# BeaglePhone_Rev2_SCH.net
KiCad netlist of a schematic drawn in Altium Designer
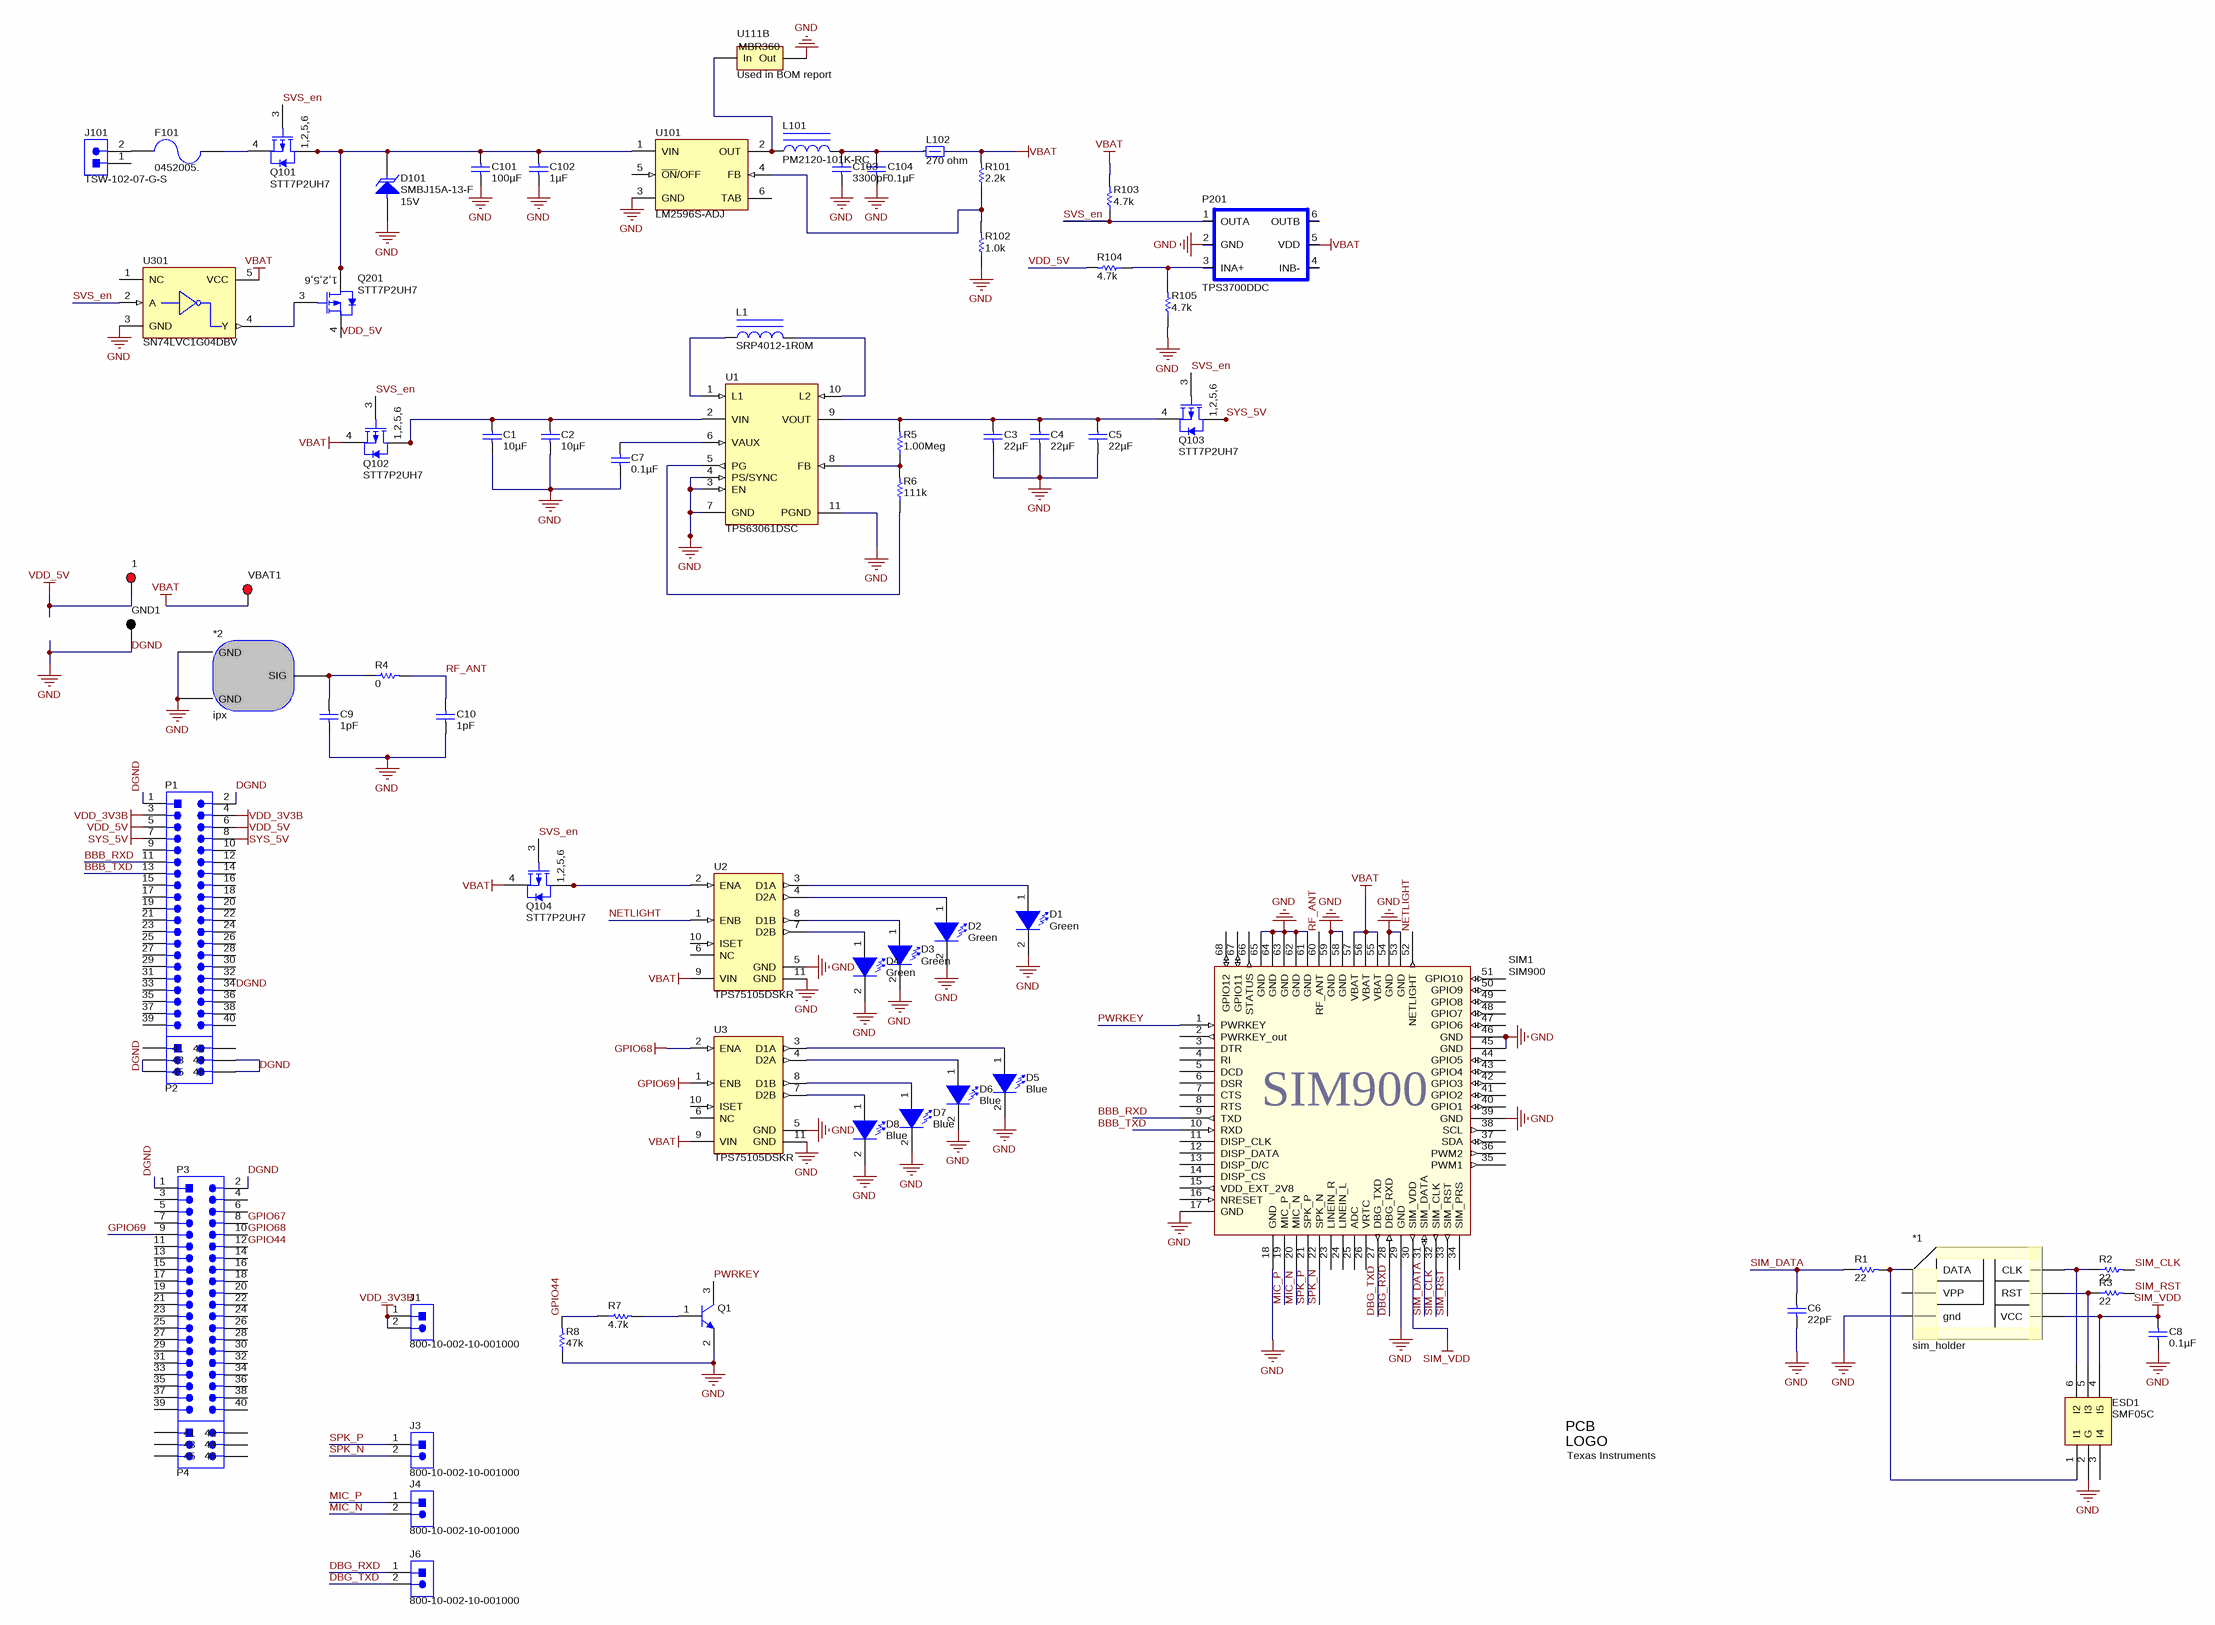
[diagram p0: BeaglePhone_Rev2_SCH.SchDoc]

(export (version "E")
  (design (tool "Eeschema 10.0.6"))
  (components
    (comp (ref "*1")
      (value "sim_holder")
      (footprint "SIM_socket")
      (libsource (lib "sim_holder") (part "sim_holder"))
    )
    (comp (ref "*2") (value "ipx") (footprint "IPX_U.FL") (libsource (lib "u.fl_IPX_connector") (part "ipx")))
    (comp (ref "1")
      (value "5005")
      (footprint "Keystone5005")
      (description "Test Point, TH, Compact, Red")
      (fields
        (field (name "MANUFACTURER") "Keystone")
        (field (name "DIGIKEYPARTNUMBER") "5005K-ND")
        (field (name "PUBLISHER") "Texas Instruments")
      )
      (libsource (lib "TemplateSCHLib") (part "5005"))
    )
    (comp (ref "C1")
      (value "C1608X5R1A106M")
      (footprint "0603")
      (description "CAP, CERM, 10uF, 10V, +/-20%, X5R, 0603")
      (fields
        (field (name "VALUEDISPLAYED") "10µF")
        (field (name "MANUFACTURER") "TDK")
        (field (name "PUBLISHER") "Texas Instruments")
      )
      (libsource (lib "Capacitor_Ceramic") (part "C1608X5R1A106M"))
    )
    (comp (ref "C2")
      (value "C1608X5R1A106M")
      (footprint "0603")
      (description "CAP, CERM, 10uF, 10V, +/-20%, X5R, 0603")
      (fields
        (field (name "VALUEDISPLAYED") "10µF")
        (field (name "MANUFACTURER") "TDK")
        (field (name "PUBLISHER") "Texas Instruments")
      )
      (libsource (lib "Capacitor_Ceramic") (part "C1608X5R1A106M"))
    )
    (comp (ref "C3")
      (value "C1608X5R0G226M080AA")
      (footprint "0603")
      (description "CAP, CERM, 22uF, 4V, +/-20%, X5R, 0603")
      (fields
        (field (name "VALUEDISPLAYED") "22µF")
        (field (name "MANUFACTURER") "TDK")
        (field (name "PUBLISHER") "Texas Instruments")
      )
      (libsource (lib "Capacitor_Ceramic") (part "C1608X5R0G226M080AA"))
    )
    (comp (ref "C4")
      (value "C1608X5R0G226M080AA")
      (footprint "0603")
      (description "CAP, CERM, 22uF, 4V, +/-20%, X5R, 0603")
      (fields
        (field (name "VALUEDISPLAYED") "22µF")
        (field (name "MANUFACTURER") "TDK")
        (field (name "PUBLISHER") "Texas Instruments")
      )
      (libsource (lib "Capacitor_Ceramic") (part "C1608X5R0G226M080AA"))
    )
    (comp (ref "C5")
      (value "C1608X5R0G226M080AA")
      (footprint "0603")
      (description "CAP, CERM, 22uF, 4V, +/-20%, X5R, 0603")
      (fields
        (field (name "VALUEDISPLAYED") "22µF")
        (field (name "MANUFACTURER") "TDK")
        (field (name "PUBLISHER") "Texas Instruments")
      )
      (libsource (lib "Capacitor_Ceramic") (part "C1608X5R0G226M080AA"))
    )
    (comp (ref "C6")
      (value "GRM1885C2A220JA01D")
      (footprint "0603")
      (description "CAP, CERM, 22pF, 100V, +/-5%, C0G/NP0, 0603")
      (fields
        (field (name "VALUEDISPLAYED") "22pF")
        (field (name "MANUFACTURER") "MuRata")
        (field (name "PUBLISHER") "Texas Instruments")
      )
      (libsource (lib "Capacitor_Ceramic") (part "GRM1885C2A220JA01D"))
    )
    (comp (ref "C7")
      (value "C0603X104K3RACTU")
      (footprint "0603")
      (description "CAP, CERM, 0.1uF, 25V, +/-10%, X7R, 0603")
      (fields
        (field (name "VALUEDISPLAYED") "0.1µF")
        (field (name "MANUFACTURER") "Kemet")
        (field (name "PUBLISHER") "Texas Instruments")
      )
      (libsource (lib "Capacitor_Ceramic") (part "C0603X104K3RACTU"))
    )
    (comp (ref "C8")
      (value "06035C104KAT2A")
      (footprint "0603")
      (description "CAP, CERM, 0.1 µF, 50 V, +/- 10%, X7R, 0603")
      (fields
        (field (name "VALUEDISPLAYED") "0.1µF")
        (field (name "MANUFACTURER") "AVX")
        (field (name "PUBLISHER") "Texas Instruments")
      )
      (libsource (lib "Capacitor_Ceramic") (part "06035C104KAT2A"))
    )
    (comp (ref "C9")
      (value "C0603C109C5GACTU")
      (footprint "0603")
      (description "CAP, CERM, 1pF, 50V, +/-25%, C0G/NP0, 0603")
      (fields
        (field (name "VALUEDISPLAYED") "1pF")
        (field (name "MANUFACTURER") "Kemet")
        (field (name "PUBLISHER") "Texas Instruments")
      )
      (libsource (lib "Capacitor_Ceramic") (part "C0603C109C5GACTU"))
    )
    (comp (ref "C10")
      (value "C0603C109C5GACTU")
      (footprint "0603")
      (description "CAP, CERM, 1pF, 50V, +/-25%, C0G/NP0, 0603")
      (fields
        (field (name "VALUEDISPLAYED") "1pF")
        (field (name "MANUFACTURER") "Kemet")
        (field (name "PUBLISHER") "Texas Instruments")
      )
      (libsource (lib "Capacitor_Ceramic") (part "C0603C109C5GACTU"))
    )
    (comp (ref "C101")
      (value "GRM31CR60J107ME39L")
      (footprint "1206")
      (description "CAP, CERM, 100uF, 6.3V, +/-20%, X5R, 1206")
      (fields
        (field (name "VALUEDISPLAYED") "100µF")
        (field (name "MANUFACTURER") "MuRata")
        (field (name "PUBLISHER") "Texas Instruments")
      )
      (libsource (lib "Capacitor_Ceramic") (part "GRM31CR60J107ME39L"))
    )
    (comp (ref "C102")
      (value "GRM188R61A105KA61D")
      (footprint "0603")
      (description "CAP, CERM, 1uF, 10V, +/-10%, X5R, 0603")
      (fields
        (field (name "VALUEDISPLAYED") "1µF")
        (field (name "MANUFACTURER") "MuRata")
        (field (name "PUBLISHER") "Texas Instruments")
      )
      (libsource (lib "Capacitor_Ceramic") (part "GRM188R61A105KA61D"))
    )
    (comp (ref "C103")
      (value "GRM188R71H332KA01D")
      (footprint "0603")
      (description "CAP, CERM, 3300pF, 50V, +/-10%, X7R, 0603")
      (fields
        (field (name "VALUEDISPLAYED") "3300pF")
        (field (name "MANUFACTURER") "MuRata")
        (field (name "PUBLISHER") "Texas Instruments")
      )
      (libsource (lib "Capacitor_Ceramic") (part "GRM188R71H332KA01D"))
    )
    (comp (ref "C104")
      (value "C0603X104K4RACTU")
      (footprint "0603")
      (description "CAP, CERM, 0.1uF, 16V, +/-10%, X7R, 0603")
      (fields
        (field (name "VALUEDISPLAYED") "0.1µF")
        (field (name "MANUFACTURER") "Kemet")
        (field (name "PUBLISHER") "Texas Instruments")
      )
      (libsource (lib "Capacitor_Ceramic") (part "C0603X104K4RACTU"))
    )
    (comp (ref "D1")
      (value "Green")
      (footprint "LG L29K_GREEN")
      (description "LED, Green, SMD")
      (fields
        (field (name "MANUFACTURER") "OSRAM")
        (field (name "PARTNUMBER") "LG L29K-G2J1-24-Z")
        (field (name "PUBLISHER") "Texas Instruments")
      )
      (libsource (lib "LED") (part "LG L29K-G2J1-24-Z"))
    )
    (comp (ref "D2")
      (value "Green")
      (footprint "LG L29K_GREEN")
      (description "LED, Green, SMD")
      (fields
        (field (name "MANUFACTURER") "OSRAM")
        (field (name "PARTNUMBER") "LG L29K-G2J1-24-Z")
        (field (name "PUBLISHER") "Texas Instruments")
      )
      (libsource (lib "LED") (part "LG L29K-G2J1-24-Z"))
    )
    (comp (ref "D3")
      (value "Green")
      (footprint "LG L29K_GREEN")
      (description "LED, Green, SMD")
      (fields
        (field (name "MANUFACTURER") "OSRAM")
        (field (name "PARTNUMBER") "LG L29K-G2J1-24-Z")
        (field (name "PUBLISHER") "Texas Instruments")
      )
      (libsource (lib "LED") (part "LG L29K-G2J1-24-Z"))
    )
    (comp (ref "D4")
      (value "Green")
      (footprint "LG L29K_GREEN")
      (description "LED, Green, SMD")
      (fields
        (field (name "MANUFACTURER") "OSRAM")
        (field (name "PARTNUMBER") "LG L29K-G2J1-24-Z")
        (field (name "PUBLISHER") "Texas Instruments")
      )
      (libsource (lib "LED") (part "LG L29K-G2J1-24-Z"))
    )
    (comp (ref "D5")
      (value "Blue")
      (footprint "LB Q39G_BLUE")
      (description "LED, Blue, SMD")
      (fields
        (field (name "MANUFACTURER") "OSRAM")
        (field (name "PARTNUMBER") "LB Q39G-L2N2-35-1")
        (field (name "PUBLISHER") "Texas Instruments")
      )
      (libsource (lib "LED") (part "LB Q39G-L2N2-35-1"))
    )
    (comp (ref "D6")
      (value "Blue")
      (footprint "LB Q39G_BLUE")
      (description "LED, Blue, SMD")
      (fields
        (field (name "MANUFACTURER") "OSRAM")
        (field (name "PARTNUMBER") "LB Q39G-L2N2-35-1")
        (field (name "PUBLISHER") "Texas Instruments")
      )
      (libsource (lib "LED") (part "LB Q39G-L2N2-35-1"))
    )
    (comp (ref "D7")
      (value "Blue")
      (footprint "LB Q39G_BLUE")
      (description "LED, Blue, SMD")
      (fields
        (field (name "MANUFACTURER") "OSRAM")
        (field (name "PARTNUMBER") "LB Q39G-L2N2-35-1")
        (field (name "PUBLISHER") "Texas Instruments")
      )
      (libsource (lib "LED") (part "LB Q39G-L2N2-35-1"))
    )
    (comp (ref "D8")
      (value "Blue")
      (footprint "LB Q39G_BLUE")
      (description "LED, Blue, SMD")
      (fields
        (field (name "MANUFACTURER") "OSRAM")
        (field (name "PARTNUMBER") "LB Q39G-L2N2-35-1")
        (field (name "PUBLISHER") "Texas Instruments")
      )
      (libsource (lib "LED") (part "LB Q39G-L2N2-35-1"))
    )
    (comp (ref "D101")
      (value "SMBJ15A-13-F")
      (footprint "SMB")
      (description "Diode, TVS, Uni, 15V, 600W, SMB")
      (fields
        (field (name "ALTIUM_VALUE") "15V")
        (field (name "MANUFACTURER") "Diodes Inc.")
        (field (name "PUBLISHER") "Texas Instruments")
      )
      (libsource (lib "ZenerDiodes") (part "SMBJ15A-13-F"))
    )
    (comp (ref "ESD1") (value "SMF05C") (footprint "6pin") (libsource (lib "SMF05C") (part "SMF05C")))
    (comp (ref "F101")
      (value "0452005.")
      (footprint "SloBlo452")
      (description "Fuse, 5A, 125V, SMD")
      (fields (field (name "MANUFACTURER") "Littelfuse") (field (name "PUBLISHER") "Texas Instruments"))
      (libsource (lib "Fuse") (part "0452005."))
    )
    (comp (ref "GND1")
      (value "5006")
      (footprint "Keystone5006")
      (description "Test Point, TH, Compact, Black")
      (fields
        (field (name "MANUFACTURER") "Keystone")
        (field (name "DIGIKEYPARTNUMBER") "5006K-ND")
        (field (name "PUBLISHER") "Texas Instruments")
      )
      (libsource (lib "TemplateSCHLib") (part "5006"))
    )
    (comp (ref "J1")
      (value "800-10-002-10-001000")
      (footprint "Mill-Max_800-10-002-10-001000")
      (description "Header, 2x1, 100mil, SMT")
      (fields
        (field (name "MANUFACTURER") "Mill-Max")
        (field (name "SYMBOLCREATOR") "a0412235")
        (field (name "PUBLISHER") "Texas Instruments")
      )
      (libsource (lib "Connectors") (part "800-10-002-10-001000"))
    )
    (comp (ref "J3")
      (value "800-10-002-10-001000")
      (footprint "Mill-Max_800-10-002-10-001000")
      (description "Header, 2x1, 100mil, SMT")
      (fields
        (field (name "MANUFACTURER") "Mill-Max")
        (field (name "SYMBOLCREATOR") "a0412235")
        (field (name "PUBLISHER") "Texas Instruments")
      )
      (libsource (lib "Connectors") (part "800-10-002-10-001000"))
    )
    (comp (ref "J4")
      (value "800-10-002-10-001000")
      (footprint "Mill-Max_800-10-002-10-001000")
      (description "Header, 2x1, 100mil, SMT")
      (fields
        (field (name "MANUFACTURER") "Mill-Max")
        (field (name "SYMBOLCREATOR") "a0412235")
        (field (name "PUBLISHER") "Texas Instruments")
      )
      (libsource (lib "Connectors") (part "800-10-002-10-001000"))
    )
    (comp (ref "J6")
      (value "800-10-002-10-001000")
      (footprint "Mill-Max_800-10-002-10-001000")
      (description "Header, 2x1, 100mil, SMT")
      (fields
        (field (name "MANUFACTURER") "Mill-Max")
        (field (name "SYMBOLCREATOR") "a0412235")
        (field (name "PUBLISHER") "Texas Instruments")
      )
      (libsource (lib "Connectors") (part "800-10-002-10-001000"))
    )
    (comp (ref "J101")
      (value "TSW-102-07-G-S")
      (footprint "TSW-102-07-G-S")
      (description "Header, 100mil, 2x1, Gold, TH")
      (fields
        (field (name "MANUFACTURER") "Samtec")
        (field (name "SYMBOLCREATOR") "a0412235")
        (field (name "PUBLISHER") "Texas Instruments")
      )
      (libsource (lib "Connectors") (part "TSW-102-07-G-S"))
    )
    (comp (ref "L1")
      (value "SRP4012-1R0M")
      (footprint "SRP4012")
      (description "Inductor, Flat Wire, Powdered Iron, 1uH, 4.8A, 0.0336 ohm, SMD")
      (fields (field (name "MANUFACTURER") "Bourns") (field (name "PUBLISHER") "Texas Instruments"))
      (libsource (lib "Inductor_Bourns") (part "SRP4012-1R0M"))
    )
    (comp (ref "L101")
      (value "PM2120-101K-RC")
      (footprint "PM2120")
      (description "Inductor, Toroid, 100uH, 6.1A, 0.035 ohm, SMD")
      (fields (field (name "MANUFACTURER") "Bourns") (field (name "PUBLISHER") "Texas Instruments"))
      (libsource (lib "Inductor_Bourns") (part "PM2120-101K-RC"))
    )
    (comp (ref "L102")
      (value "270 ohm")
      (footprint "2220")
      (description "Ferrite Bead, 270 ohm @ 100MHz, 4A, 2220")
      (fields
        (field (name "PARTNUMBER") "HI2220P271R-10")
        (field (name "MANUFACTURER") "Laird-Signal Integrity Products")
        (field (name "PUBLISHER") "Texas Instruments")
      )
      (libsource (lib "FerriteBead") (part "HI2220P271R-10"))
    )
    (comp (ref "Logo1")
      (value "Texas Instruments")
      (footprint "TI_Symbol_Overlay_Small")
      (description "Texas Instrument Corporate Signature")
      (fields (field (name "SYMBOLCREATOR") "codlsc") (field (name "PUBLISHER") "Texas Instruments"))
      (libsource (lib "Logos") (part "TI_Logo"))
    )
    (comp (ref "P1")
      (value "Comment")
      (footprint "TSW-120-07-G-D")
      (description "Header, 100mil, 20x2, Gold, TH")
      (fields
        (field (name "PARTNUMBER") "TSW-120-07-G-D")
        (field (name "MANUFACTURER") "Samtec")
        (field (name "SYMBOLCREATOR") "a0412235")
        (field (name "PUBLISHER") "Texas Instruments")
      )
      (libsource (lib "Connectors") (part "TSW-120-07-G-D"))
    )
    (comp (ref "P2")
      (value "Comment")
      (footprint "SULLINS_PEC03DAAN")
      (description "Header, 100mil, 3x2, Tin, TH")
      (fields
        (field (name "PARTNUMBER") "PEC03DAAN")
        (field (name "MANUFACTURER") "Sullins Connector Solutions")
        (field (name "SYMBOLCREATOR") "a0412235")
        (field (name "PUBLISHER") "Texas Instruments")
      )
      (libsource (lib "Connectors") (part "PEC03DAAN"))
    )
    (comp (ref "P3")
      (value "Comment")
      (footprint "TSW-120-07-G-D")
      (description "Header, 100mil, 20x2, Gold, TH")
      (fields
        (field (name "PARTNUMBER") "TSW-120-07-G-D")
        (field (name "MANUFACTURER") "Samtec")
        (field (name "SYMBOLCREATOR") "a0412235")
        (field (name "PUBLISHER") "Texas Instruments")
      )
      (libsource (lib "Connectors") (part "TSW-120-07-G-D"))
    )
    (comp (ref "P4")
      (value "Comment")
      (footprint "SULLINS_PEC03DAAN")
      (description "Header, 100mil, 3x2, Tin, TH")
      (fields
        (field (name "PARTNUMBER") "PEC03DAAN")
        (field (name "MANUFACTURER") "Sullins Connector Solutions")
        (field (name "SYMBOLCREATOR") "a0412235")
        (field (name "PUBLISHER") "Texas Instruments")
      )
      (libsource (lib "Connectors") (part "PEC03DAAN"))
    )
    (comp (ref "P201")
      (value "TPS3700DDC")
      (footprint "SOT23-6")
      (description "IC,  High Voltage, Over-Under Voltage Supervisory")
      (fields (field (name "MANUFACTURER") "TI"))
      (libsource (lib "PADSlegacy_PMP") (part "TPS3700DDC"))
    )
    (comp (ref "Q1")
      (value "MMBT2222LT1G")
      (footprint "SOT-23")
      (description "Transistor, NPN, 30V, 0.6A, SOT-23")
      (fields (field (name "MANUFACTURER") "ON Semiconductor") (field (name "PUBLISHER") "Texas Instruments"))
      (libsource (lib "Bipolar_Transistor") (part "MMBT2222LT1G, ON Semiconductor"))
    )
    (comp (ref "Q101")
      (value "STT7P2UH7")
      (footprint "SOT-23-6")
      (description "MOSFET, P-CH, 60V, -3A, SOT-23-6")
      (fields
        (field (name "MANUFACTURER") "Fairchild Semiconductor")
        (field (name "PUBLISHER") "Texas Instruments")
      )
      (libsource (lib "FETs") (part "FDC5614P"))
    )
    (comp (ref "Q102")
      (value "STT7P2UH7")
      (footprint "SOT-23-6")
      (description "MOSFET, P-CH, 60V, -3A, SOT-23-6")
      (fields
        (field (name "MANUFACTURER") "Fairchild Semiconductor")
        (field (name "PUBLISHER") "Texas Instruments")
      )
      (libsource (lib "FETs") (part "FDC5614P"))
    )
    (comp (ref "Q103")
      (value "STT7P2UH7")
      (footprint "SOT-23-6")
      (description "MOSFET, P-CH, 60V, -3A, SOT-23-6")
      (fields
        (field (name "MANUFACTURER") "Fairchild Semiconductor")
        (field (name "PUBLISHER") "Texas Instruments")
      )
      (libsource (lib "FETs") (part "FDC5614P"))
    )
    (comp (ref "Q104")
      (value "STT7P2UH7")
      (footprint "SOT-23-6")
      (description "MOSFET, P-CH, 60V, -3A, SOT-23-6")
      (fields
        (field (name "MANUFACTURER") "Fairchild Semiconductor")
        (field (name "PUBLISHER") "Texas Instruments")
      )
      (libsource (lib "FETs") (part "FDC5614P"))
    )
    (comp (ref "Q201")
      (value "STT7P2UH7")
      (footprint "SOT-23-6")
      (description "MOSFET, P-CH, 60V, -3A, SOT-23-6")
      (fields
        (field (name "MANUFACTURER") "Fairchild Semiconductor")
        (field (name "PUBLISHER") "Texas Instruments")
      )
      (libsource (lib "FETs") (part "FDC5614P"))
    )
    (comp (ref "R1")
      (value "22")
      (footprint "0603")
      (description "RES, 22 ohm, 5%, 0.1W, 0603")
      (fields
        (field (name "PARTNUMBER") "CRCW060322R0JNEA")
        (field (name "MANUFACTURER") "Vishay-Dale")
        (field (name "PUBLISHER") "Texas Instruments")
      )
      (libsource (lib "Resistor_0603") (part "CRCW060322R0JNEA"))
    )
    (comp (ref "R2")
      (value "22")
      (footprint "0603")
      (description "RES, 22 ohm, 5%, 0.1W, 0603")
      (fields
        (field (name "PARTNUMBER") "CRCW060322R0JNEA")
        (field (name "MANUFACTURER") "Vishay-Dale")
        (field (name "PUBLISHER") "Texas Instruments")
      )
      (libsource (lib "Resistor_0603") (part "CRCW060322R0JNEA"))
    )
    (comp (ref "R3")
      (value "22")
      (footprint "0603")
      (description "RES, 22 ohm, 5%, 0.1W, 0603")
      (fields
        (field (name "PARTNUMBER") "CRCW060322R0JNEA")
        (field (name "MANUFACTURER") "Vishay-Dale")
        (field (name "PUBLISHER") "Texas Instruments")
      )
      (libsource (lib "Resistor_0603") (part "CRCW060322R0JNEA"))
    )
    (comp (ref "R4")
      (value "0")
      (footprint "0805_HV")
      (description "RES, 0 ohm, 5%, 0.333W, 0805")
      (fields
        (field (name "PARTNUMBER") "CRCW08050000Z0EAHP")
        (field (name "MANUFACTURER") "Vishay-Dale")
        (field (name "PUBLISHER") "Texas Instruments")
      )
      (libsource (lib "Resistor_0805") (part "CRCW08050000Z0EAHP"))
    )
    (comp (ref "R5")
      (value "1.00Meg")
      (footprint "0603")
      (description "RES, 1.00Meg ohm, 1%, 0.1W, 0603")
      (fields
        (field (name "PARTNUMBER") "CRCW06031M00FKEA")
        (field (name "MANUFACTURER") "Vishay-Dale")
        (field (name "PUBLISHER") "Texas Instruments")
      )
      (libsource (lib "Resistor_0603") (part "CRCW06031M00FKEA"))
    )
    (comp (ref "R6")
      (value "111k")
      (footprint "0603")
      (description "RES, 111k ohm, 0.1%, 0.1W, 0603")
      (fields
        (field (name "PARTNUMBER") "RT0603BRD07111KL")
        (field (name "MANUFACTURER") "Yageo America")
        (field (name "PUBLISHER") "Texas Instruments")
      )
      (libsource (lib "Resistor_0603") (part "RT0603BRD07111KL"))
    )
    (comp (ref "R7")
      (value "CRCW04024K70JNED")
      (footprint "0402")
      (description "RES, 4.7 k, 5%, 0.063 W, 0402")
      (fields
        (field (name "VALUEDISPLAYED") "4.7k")
        (field (name "MANUFACTURER") "Vishay-Dale")
        (field (name "PUBLISHER") "Texas Instruments")
      )
      (libsource (lib "Resistor_0402") (part "CRCW04024K70JNED"))
    )
    (comp (ref "R8")
      (value "CRCW04024K70JNED")
      (footprint "0402")
      (description "RES, 4.7 k, 5%, 0.063 W, 0402")
      (fields
        (field (name "VALUEDISPLAYED") "47k")
        (field (name "MANUFACTURER") "Vishay-Dale")
        (field (name "PUBLISHER") "Texas Instruments")
      )
      (libsource (lib "Resistor_0402") (part "CRCW04024K70JNED"))
    )
    (comp (ref "R101")
      (value "2.2k")
      (footprint "0603")
      (description "RES, 2.2k ohm, 5%, 0.1W, 0603")
      (fields
        (field (name "PARTNUMBER") "CRCW06032K20JNEA")
        (field (name "MANUFACTURER") "Vishay-Dale")
        (field (name "PUBLISHER") "Texas Instruments")
      )
      (libsource (lib "Resistor_0603") (part "CRCW06032K20JNEA"))
    )
    (comp (ref "R102")
      (value "1.0k")
      (footprint "0603")
      (description "RES, 1.0k ohm, 5%, 0.1W, 0603")
      (fields
        (field (name "PARTNUMBER") "CRCW06031K00JNEA")
        (field (name "MANUFACTURER") "Vishay-Dale")
        (field (name "PUBLISHER") "Texas Instruments")
      )
      (libsource (lib "Resistor_0603") (part "CRCW06031K00JNEA"))
    )
    (comp (ref "R103")
      (value "4.7k")
      (footprint "0603")
      (description "RES, 4.7k ohm, 5%, 0.1W, 0603")
      (fields
        (field (name "PARTNUMBER") "CRCW06034K70JNEA")
        (field (name "MANUFACTURER") "Vishay-Dale")
        (field (name "PUBLISHER") "Texas Instruments")
      )
      (libsource (lib "Resistor_0603") (part "CRCW06034K70JNEA"))
    )
    (comp (ref "R104")
      (value "4.7k")
      (footprint "0603")
      (description "RES, 4.7k ohm, 5%, 0.1W, 0603")
      (fields
        (field (name "PARTNUMBER") "CRCW06034K70JNEA")
        (field (name "MANUFACTURER") "Vishay-Dale")
        (field (name "PUBLISHER") "Texas Instruments")
      )
      (libsource (lib "Resistor_0603") (part "CRCW06034K70JNEA"))
    )
    (comp (ref "R105")
      (value "4.7k")
      (footprint "0603")
      (description "RES, 4.7k ohm, 5%, 0.1W, 0603")
      (fields
        (field (name "PARTNUMBER") "CRCW06034K70JNEA")
        (field (name "MANUFACTURER") "Vishay-Dale")
        (field (name "PUBLISHER") "Texas Instruments")
      )
      (libsource (lib "Resistor_0603") (part "CRCW06034K70JNEA"))
    )
    (comp (ref "SIM1")
      (value "SIM900")
      (footprint "PCBComponent_1 - duplicate1")
      (libsource (lib "Schematic Components") (part "SIM900"))
    )
    (comp (ref "U1")
      (value "TPS63061DSC")
      (footprint "DSC0010E")
      (description "HIGH INPUT VOLTAGE BUCK-BOOST CONVERTER WITH 2A SWITCH CURRENT, DSC0010E")
      (fields
        (field (name "MANUFACTURER") "Texas Instruments")
        (field (name "SYMBOLCREATOR") "a0411947")
        (field (name "PUBLISHER") "Texas Instruments")
      )
      (libsource (lib "TI_Pre_Release") (part "TPS63061DSC"))
    )
    (comp (ref "U2")
      (value "TPS75105DSKR")
      (footprint "DSK0010A")
      (fields
        (field (name "MANUFACTURER") "Texas Instruments")
        (field (name "ALTERNATE PARTNUMBER") "Equivalent")
      )
      (libsource (lib "TI Power Management Lighting and Display") (part "TPS75105DSKR"))
    )
    (comp (ref "U3")
      (value "TPS75105DSKR")
      (footprint "DSK0010A")
      (fields
        (field (name "MANUFACTURER") "Texas Instruments")
        (field (name "ALTERNATE PARTNUMBER") "Equivalent")
      )
      (libsource (lib "TI Power Management Lighting and Display") (part "TPS75105DSKR"))
    )
    (comp (ref "U101")
      (value "LM2596S-ADJ")
      (footprint "TS5B_N")
      (description "SIMPLE SWITCHER® Power Converter 150 KHz 3A Step-Down Voltage Regulator, 5-pin TO-263")
      (fields
        (field (name "MANUFACTURER") "National Semiconductor")
        (field (name "PUBLISHER") "Altium Limited")
      )
      (libsource (lib "NSC Switcher") (part "LM2596S-ADJ"))
    )
    (comp (ref "U111")
      (value "Used in BOM report")
      (footprint "PCBComponent_1 - duplicate2")
      (fields (field (name "SYMBOLCREATOR") "Use a-id"))
      (libsource (lib "josh") (part "MBR360"))
    )
    (comp (ref "U301")
      (value "SN74LVC1G04DBV")
      (footprint "DBV0005A_N")
      (description "Single Inverter Gate, DBV0005A")
      (fields
        (field (name "MANUFACTURER") "Texas Instruments")
        (field (name "SYMBOLCREATOR") "a0411947")
        (field (name "PUBLISHER") "Texas Instruments")
      )
      (libsource (lib "TI_Pre_Release") (part "SN74LVC1G04DBV"))
    )
    (comp (ref "VBAT1")
      (value "5005")
      (footprint "Keystone5005")
      (description "Test Point, TH, Compact, Red")
      (fields
        (field (name "MANUFACTURER") "Keystone")
        (field (name "DIGIKEYPARTNUMBER") "5005K-ND")
        (field (name "PUBLISHER") "Texas Instruments")
      )
      (libsource (lib "TemplateSCHLib") (part "5005"))
    )
  )
  (nets
    (net (code "2") (name "/BBB_RXD") (class "Default")
      (node (ref "P1") (pin "11") (pinfunction "11_11") (pintype "passive"))
    )
    (net (code "3") (name "/BBB_TXD") (class "Default")
      (node (ref "P1") (pin "13") (pinfunction "13_13") (pintype "passive"))
    )
    (net (code "4") (name "/DBG_RXD") (class "Default")
      (node (ref "J6") (pin "1") (pinfunction "1_1") (pintype "passive"))
      (node (ref "SIM1") (pin "28") (pinfunction "DBG_RXD_28") (pintype "input"))
    )
    (net (code "5") (name "/DBG_TXD") (class "Default")
      (node (ref "J6") (pin "2") (pinfunction "2_2") (pintype "passive"))
      (node (ref "SIM1") (pin "27") (pinfunction "DBG_TXD_27") (pintype "output"))
    )
    (net (code "6") (name "/GPIO44") (class "Default")
      (node (ref "P3") (pin "12") (pinfunction "12_12") (pintype "passive"))
      (node (ref "R7") (pin "1") (pinfunction "1_1") (pintype "passive"))
      (node (ref "R8") (pin "2") (pinfunction "2_2") (pintype "passive"))
    )
    (net (code "7") (name "/GPIO67") (class "Default")
      (node (ref "P3") (pin "8") (pinfunction "8_8") (pintype "passive"))
    )
    (net (code "8") (name "/MIC_N") (class "Default")
      (node (ref "J4") (pin "2") (pinfunction "2_2") (pintype "passive"))
      (node (ref "SIM1") (pin "20") (pinfunction "MIC_N_20") (pintype "passive"))
    )
    (net (code "9") (name "/MIC_P") (class "Default")
      (node (ref "J4") (pin "1") (pinfunction "1_1") (pintype "passive"))
      (node (ref "SIM1") (pin "19") (pinfunction "MIC_P_19") (pintype "passive"))
    )
    (net (code "10") (name "/NETLIGHT") (class "Default")
      (node (ref "SIM1") (pin "52") (pinfunction "NETLIGHT_52") (pintype "output"))
      (node (ref "U2") (pin "1") (pinfunction "ENB_1") (pintype "input"))
    )
    (net (code "11") (name "/PWRKEY") (class "Default")
      (node (ref "Q1") (pin "3") (pinfunction "C_3") (pintype "passive"))
      (node (ref "SIM1") (pin "1") (pinfunction "PWRKEY_1") (pintype "input"))
    )
    (net (code "12") (name "/RF_ANT") (class "Default")
      (node (ref "C10") (pin "1") (pinfunction "1_1") (pintype "passive"))
      (node (ref "R4") (pin "2") (pinfunction "2_2") (pintype "passive"))
      (node (ref "SIM1") (pin "60") (pinfunction "RF_ANT_60") (pintype "passive"))
    )
    (net (code "13") (name "/SIM_CLK") (class "Default")
      (node (ref "R2") (pin "2") (pinfunction "2_2") (pintype "passive"))
      (node (ref "SIM1") (pin "32") (pinfunction "SIM_CLK_32") (pintype "output"))
    )
    (net (code "14") (name "/SIM_DATA") (class "Default")
      (node (ref "C6") (pin "1") (pinfunction "1_1") (pintype "passive"))
      (node (ref "R1") (pin "1") (pinfunction "1_1") (pintype "passive"))
      (node (ref "SIM1") (pin "31") (pinfunction "SIM_DATA_31") (pintype "bidirectional"))
    )
    (net (code "15") (name "/SIM_RST") (class "Default")
      (node (ref "R3") (pin "2") (pinfunction "2_2") (pintype "passive"))
      (node (ref "SIM1") (pin "33") (pinfunction "SIM_RST_33") (pintype "output"))
    )
    (net (code "16") (name "/SPK_N") (class "Default")
      (node (ref "J3") (pin "2") (pinfunction "2_2") (pintype "passive"))
      (node (ref "SIM1") (pin "22") (pinfunction "SPK_N_22") (pintype "passive"))
    )
    (net (code "17") (name "/SPK_P") (class "Default")
      (node (ref "J3") (pin "1") (pinfunction "1_1") (pintype "passive"))
      (node (ref "SIM1") (pin "21") (pinfunction "SPK_P_21") (pintype "passive"))
    )
    (net (code "18") (name "/SVS_en") (class "Default")
      (node (ref "P201") (pin "1") (pinfunction "OUTA_1") (pintype "passive"))
      (node (ref "Q101") (pin "3") (pinfunction "G_3") (pintype "passive"))
      (node (ref "Q102") (pin "3") (pinfunction "G_3") (pintype "passive"))
      (node (ref "Q103") (pin "3") (pinfunction "G_3") (pintype "passive"))
      (node (ref "Q104") (pin "3") (pinfunction "G_3") (pintype "passive"))
      (node (ref "R103") (pin "1") (pinfunction "1_1") (pintype "passive"))
      (node (ref "U301") (pin "2") (pinfunction "A_2") (pintype "input"))
    )
    (net (code "19") (name "GND") (class "Default")
      (node (ref "*1") (pin "1") (pinfunction "gnd_1") (pintype "passive"))
      (node (ref "*2") (pin "1") (pinfunction "GND_1") (pintype "passive"))
      (node (ref "*2") (pin "2") (pinfunction "GND_2") (pintype "passive"))
      (node (ref "C1") (pin "1") (pinfunction "1_1") (pintype "passive"))
      (node (ref "C10") (pin "2") (pinfunction "2_2") (pintype "passive"))
      (node (ref "C101") (pin "2") (pinfunction "2_2") (pintype "passive"))
      (node (ref "C102") (pin "2") (pinfunction "2_2") (pintype "passive"))
      (node (ref "C103") (pin "2") (pinfunction "2_2") (pintype "passive"))
      (node (ref "C104") (pin "2") (pinfunction "2_2") (pintype "passive"))
      (node (ref "C2") (pin "1") (pinfunction "1_1") (pintype "passive"))
      (node (ref "C3") (pin "1") (pinfunction "1_1") (pintype "passive"))
      (node (ref "C4") (pin "1") (pinfunction "1_1") (pintype "passive"))
      (node (ref "C5") (pin "1") (pinfunction "1_1") (pintype "passive"))
      (node (ref "C6") (pin "2") (pinfunction "2_2") (pintype "passive"))
      (node (ref "C7") (pin "2") (pinfunction "2_2") (pintype "passive"))
      (node (ref "C8") (pin "2") (pinfunction "2_2") (pintype "passive"))
      (node (ref "C9") (pin "2") (pinfunction "2_2") (pintype "passive"))
      (node (ref "D1") (pin "2") (pinfunction "K_2") (pintype "passive"))
      (node (ref "D101") (pin "2") (pinfunction "A_2") (pintype "passive"))
      (node (ref "D2") (pin "2") (pinfunction "K_2") (pintype "passive"))
      (node (ref "D3") (pin "2") (pinfunction "K_2") (pintype "passive"))
      (node (ref "D4") (pin "2") (pinfunction "K_2") (pintype "passive"))
      (node (ref "D5") (pin "2") (pinfunction "K_2") (pintype "passive"))
      (node (ref "D6") (pin "2") (pinfunction "K_2") (pintype "passive"))
      (node (ref "D7") (pin "2") (pinfunction "K_2") (pintype "passive"))
      (node (ref "D8") (pin "2") (pinfunction "K_2") (pintype "passive"))
      (node (ref "ESD1") (pin "2") (pinfunction "G_2") (pintype "passive"))
      (node (ref "GND1") (pin "1") (pintype "passive"))
      (node (ref "P1") (pin "1") (pinfunction "1_1") (pintype "passive"))
      (node (ref "P1") (pin "2") (pinfunction "2_2") (pintype "passive"))
      (node (ref "P1") (pin "34") (pinfunction "34_34") (pintype "passive"))
      (node (ref "P2") (pin "3") (pinfunction "43_3") (pintype "passive"))
      (node (ref "P2") (pin "4") (pinfunction "44_4") (pintype "passive"))
      (node (ref "P2") (pin "5") (pinfunction "45_5") (pintype "passive"))
      (node (ref "P2") (pin "6") (pinfunction "46_6") (pintype "passive"))
      (node (ref "P201") (pin "2") (pinfunction "GND_2") (pintype "passive"))
      (node (ref "P3") (pin "1") (pinfunction "1_1") (pintype "passive"))
      (node (ref "P3") (pin "2") (pinfunction "2_2") (pintype "passive"))
      (node (ref "Q1") (pin "2") (pinfunction "E_2") (pintype "passive"))
      (node (ref "R102") (pin "1") (pinfunction "1_1") (pintype "passive"))
      (node (ref "R105") (pin "1") (pinfunction "1_1") (pintype "passive"))
      (node (ref "R8") (pin "1") (pinfunction "1_1") (pintype "passive"))
      (node (ref "SIM1") (pin "17") (pinfunction "GND_17") (pintype "passive"))
      (node (ref "SIM1") (pin "18") (pinfunction "GND_18") (pintype "passive"))
      (node (ref "SIM1") (pin "29") (pinfunction "GND_29") (pintype "passive"))
      (node (ref "SIM1") (pin "39") (pinfunction "GND_39") (pintype "passive"))
      (node (ref "SIM1") (pin "45") (pinfunction "GND_45") (pintype "passive"))
      (node (ref "SIM1") (pin "46") (pinfunction "GND_46") (pintype "passive"))
      (node (ref "SIM1") (pin "53") (pinfunction "GND_53") (pintype "passive"))
      (node (ref "SIM1") (pin "54") (pinfunction "GND_54") (pintype "passive"))
      (node (ref "SIM1") (pin "58") (pinfunction "GND_58") (pintype "passive"))
      (node (ref "SIM1") (pin "59") (pinfunction "GND_59") (pintype "passive"))
      (node (ref "SIM1") (pin "61") (pinfunction "GND_61") (pintype "passive"))
      (node (ref "SIM1") (pin "62") (pinfunction "GND_62") (pintype "passive"))
      (node (ref "SIM1") (pin "63") (pinfunction "GND_63") (pintype "passive"))
      (node (ref "SIM1") (pin "64") (pinfunction "GND_64") (pintype "passive"))
      (node (ref "SIM1") (pin "65") (pinfunction "GND_65") (pintype "passive"))
      (node (ref "U1") (pin "11") (pinfunction "PGND_11") (pintype "power_in"))
      (node (ref "U1") (pin "3") (pinfunction "EN_3") (pintype "input"))
      (node (ref "U1") (pin "4") (pinfunction "PS/SYNC_4") (pintype "input"))
      (node (ref "U1") (pin "7") (pinfunction "GND_7") (pintype "power_in"))
      (node (ref "U101") (pin "3") (pinfunction "GND_3") (pintype "power_in"))
      (node (ref "U111") (pin "2") (pinfunction "Out_2") (pintype "passive"))
      (node (ref "U2") (pin "11") (pinfunction "GND_11") (pintype "power_in"))
      (node (ref "U2") (pin "5") (pinfunction "GND_5") (pintype "power_in"))
      (node (ref "U3") (pin "11") (pinfunction "GND_11") (pintype "power_in"))
      (node (ref "U3") (pin "5") (pinfunction "GND_5") (pintype "power_in"))
      (node (ref "U301") (pin "3") (pinfunction "GND_3") (pintype "power_in"))
    )
    (net (code "20") (name "GPIO68") (class "Default")
      (node (ref "P3") (pin "10") (pinfunction "10_10") (pintype "passive"))
      (node (ref "U3") (pin "2") (pinfunction "ENA_2") (pintype "input"))
    )
    (net (code "21") (name "GPIO69") (class "Default")
      (node (ref "P3") (pin "9") (pinfunction "9_9") (pintype "passive"))
      (node (ref "U3") (pin "1") (pinfunction "ENB_1") (pintype "input"))
    )
    (net (code "22") (name "Net-(*1-CLK)") (class "Default")
      (node (ref "*1") (pin "4") (pinfunction "CLK_4") (pintype "passive"))
      (node (ref "ESD1") (pin "6") (pinfunction "I2_6") (pintype "passive"))
      (node (ref "R2") (pin "1") (pinfunction "1_1") (pintype "passive"))
    )
    (net (code "23") (name "Net-(*1-DATA)") (class "Default")
      (node (ref "*1") (pin "3") (pinfunction "DATA_3") (pintype "passive"))
      (node (ref "ESD1") (pin "1") (pinfunction "I1_1") (pintype "passive"))
      (node (ref "R1") (pin "2") (pinfunction "2_2") (pintype "passive"))
    )
    (net (code "24") (name "Net-(*1-RST)") (class "Default")
      (node (ref "*1") (pin "5") (pinfunction "RST_5") (pintype "passive"))
      (node (ref "ESD1") (pin "5") (pinfunction "I3_5") (pintype "passive"))
      (node (ref "R3") (pin "1") (pinfunction "1_1") (pintype "passive"))
    )
    (net (code "25") (name "Net-(*2-SIG)") (class "Default")
      (node (ref "*2") (pin "3") (pinfunction "SIG_3") (pintype "passive"))
      (node (ref "C9") (pin "1") (pinfunction "1_1") (pintype "passive"))
      (node (ref "R4") (pin "1") (pinfunction "1_1") (pintype "passive"))
    )
    (net (code "26") (name "Net-(C103-Pad1)") (class "Default")
      (node (ref "C103") (pin "1") (pinfunction "1_1") (pintype "passive"))
      (node (ref "C104") (pin "1") (pinfunction "1_1") (pintype "passive"))
      (node (ref "L101") (pin "2") (pinfunction "2_2") (pintype "passive"))
      (node (ref "L102") (pin "1") (pinfunction "1_1") (pintype "passive"))
    )
    (net (code "27") (name "Net-(D1-A)") (class "Default")
      (node (ref "D1") (pin "1") (pinfunction "A_1") (pintype "passive"))
      (node (ref "U2") (pin "3") (pinfunction "D1A_3") (pintype "output"))
    )
    (net (code "28") (name "Net-(D2-A)") (class "Default")
      (node (ref "D2") (pin "1") (pinfunction "A_1") (pintype "passive"))
      (node (ref "U2") (pin "4") (pinfunction "D2A_4") (pintype "output"))
    )
    (net (code "29") (name "Net-(D3-A)") (class "Default")
      (node (ref "D3") (pin "1") (pinfunction "A_1") (pintype "passive"))
      (node (ref "U2") (pin "8") (pinfunction "D1B_8") (pintype "output"))
    )
    (net (code "30") (name "Net-(D4-A)") (class "Default")
      (node (ref "D4") (pin "1") (pinfunction "A_1") (pintype "passive"))
      (node (ref "U2") (pin "7") (pinfunction "D2B_7") (pintype "output"))
    )
    (net (code "31") (name "Net-(D5-A)") (class "Default")
      (node (ref "D5") (pin "1") (pinfunction "A_1") (pintype "passive"))
      (node (ref "U3") (pin "3") (pinfunction "D1A_3") (pintype "output"))
    )
    (net (code "32") (name "Net-(D6-A)") (class "Default")
      (node (ref "D6") (pin "1") (pinfunction "A_1") (pintype "passive"))
      (node (ref "U3") (pin "4") (pinfunction "D2A_4") (pintype "output"))
    )
    (net (code "33") (name "Net-(D7-A)") (class "Default")
      (node (ref "D7") (pin "1") (pinfunction "A_1") (pintype "passive"))
      (node (ref "U3") (pin "8") (pinfunction "D1B_8") (pintype "output"))
    )
    (net (code "34") (name "Net-(D8-A)") (class "Default")
      (node (ref "D8") (pin "1") (pinfunction "A_1") (pintype "passive"))
      (node (ref "U3") (pin "7") (pinfunction "D2B_7") (pintype "output"))
    )
    (net (code "35") (name "Net-(D101-K)") (class "Default")
      (node (ref "C101") (pin "1") (pinfunction "1_1") (pintype "passive"))
      (node (ref "C102") (pin "1") (pinfunction "1_1") (pintype "passive"))
      (node (ref "D101") (pin "1") (pinfunction "K_1") (pintype "passive"))
      (node (ref "Q101") (pin "1") (pinfunction "D_1") (pintype "passive"))
      (node (ref "Q101") (pin "2") (pinfunction "D_2") (pintype "passive"))
      (node (ref "Q101") (pin "5") (pinfunction "D_5") (pintype "passive"))
      (node (ref "Q101") (pin "6") (pinfunction "D_6") (pintype "passive"))
      (node (ref "Q201") (pin "1") (pinfunction "D_1") (pintype "passive"))
      (node (ref "Q201") (pin "2") (pinfunction "D_2") (pintype "passive"))
      (node (ref "Q201") (pin "5") (pinfunction "D_5") (pintype "passive"))
      (node (ref "Q201") (pin "6") (pinfunction "D_6") (pintype "passive"))
      (node (ref "U101") (pin "1") (pinfunction "VIN_1") (pintype "power_in"))
    )
    (net (code "36") (name "Net-(F101-Pad2)") (class "Default")
      (node (ref "F101") (pin "2") (pinfunction "2_2") (pintype "passive"))
      (node (ref "J101") (pin "2") (pinfunction "2_2") (pintype "passive"))
    )
    (net (code "37") (name "Net-(P201-INA+)") (class "Default")
      (node (ref "P201") (pin "3") (pinfunction "INA+_3") (pintype "passive"))
      (node (ref "R104") (pin "1") (pinfunction "1_1") (pintype "passive"))
      (node (ref "R105") (pin "2") (pinfunction "2_2") (pintype "passive"))
    )
    (net (code "38") (name "Net-(Q1-B)") (class "Default")
      (node (ref "Q1") (pin "1") (pinfunction "B_1") (pintype "passive"))
      (node (ref "R7") (pin "2") (pinfunction "2_2") (pintype "passive"))
    )
    (net (code "39") (name "Net-(Q101-S)") (class "Default")
      (node (ref "F101") (pin "1") (pinfunction "1_1") (pintype "passive"))
      (node (ref "Q101") (pin "4") (pinfunction "S_4") (pintype "passive"))
    )
    (net (code "40") (name "Net-(Q103-S)") (class "Default")
      (node (ref "C3") (pin "2") (pinfunction "2_2") (pintype "passive"))
      (node (ref "C4") (pin "2") (pinfunction "2_2") (pintype "passive"))
      (node (ref "C5") (pin "2") (pinfunction "2_2") (pintype "passive"))
      (node (ref "Q103") (pin "4") (pinfunction "S_4") (pintype "passive"))
      (node (ref "R5") (pin "2") (pinfunction "2_2") (pintype "passive"))
      (node (ref "U1") (pin "9") (pinfunction "VOUT_9") (pintype "power_in"))
    )
    (net (code "41") (name "Net-(Q201-G)") (class "Default")
      (node (ref "Q201") (pin "3") (pinfunction "G_3") (pintype "passive"))
      (node (ref "U301") (pin "4") (pinfunction "Y_4") (pintype "output"))
    )
    (net (code "42") (name "Net-(U1-FB)") (class "Default")
      (node (ref "R5") (pin "1") (pinfunction "1_1") (pintype "passive"))
      (node (ref "R6") (pin "2") (pinfunction "2_2") (pintype "passive"))
      (node (ref "U1") (pin "8") (pinfunction "FB_8") (pintype "input"))
    )
    (net (code "43") (name "Net-(U1-L1)") (class "Default")
      (node (ref "L1") (pin "1") (pinfunction "1_1") (pintype "passive"))
      (node (ref "U1") (pin "1") (pinfunction "L1_1") (pintype "input"))
    )
    (net (code "44") (name "Net-(U1-L2)") (class "Default")
      (node (ref "L1") (pin "2") (pinfunction "2_2") (pintype "passive"))
      (node (ref "U1") (pin "10") (pinfunction "L2_10") (pintype "input"))
    )
    (net (code "45") (name "Net-(U1-PG)") (class "Default")
      (node (ref "R6") (pin "1") (pinfunction "1_1") (pintype "passive"))
      (node (ref "U1") (pin "5") (pinfunction "PG_5") (pintype "output"))
    )
    (net (code "46") (name "Net-(U1-VAUX)") (class "Default")
      (node (ref "C7") (pin "1") (pinfunction "1_1") (pintype "passive"))
      (node (ref "U1") (pin "6") (pinfunction "VAUX_6") (pintype "input"))
    )
    (net (code "47") (name "Net-(U1-VIN)") (class "Default")
      (node (ref "C1") (pin "2") (pinfunction "2_2") (pintype "passive"))
      (node (ref "C2") (pin "2") (pinfunction "2_2") (pintype "passive"))
      (node (ref "Q102") (pin "1") (pinfunction "D_1") (pintype "passive"))
      (node (ref "Q102") (pin "2") (pinfunction "D_2") (pintype "passive"))
      (node (ref "Q102") (pin "5") (pinfunction "D_5") (pintype "passive"))
      (node (ref "Q102") (pin "6") (pinfunction "D_6") (pintype "passive"))
      (node (ref "U1") (pin "2") (pinfunction "VIN_2") (pintype "power_in"))
    )
    (net (code "48") (name "Net-(U2-ENA)") (class "Default")
      (node (ref "Q104") (pin "1") (pinfunction "D_1") (pintype "passive"))
      (node (ref "Q104") (pin "2") (pinfunction "D_2") (pintype "passive"))
      (node (ref "Q104") (pin "5") (pinfunction "D_5") (pintype "passive"))
      (node (ref "Q104") (pin "6") (pinfunction "D_6") (pintype "passive"))
      (node (ref "U2") (pin "2") (pinfunction "ENA_2") (pintype "input"))
    )
    (net (code "49") (name "Net-(U101-FB)") (class "Default")
      (node (ref "R101") (pin "1") (pinfunction "1_1") (pintype "passive"))
      (node (ref "R102") (pin "2") (pinfunction "2_2") (pintype "passive"))
      (node (ref "U101") (pin "4") (pinfunction "FB_4") (pintype "input"))
    )
    (net (code "50") (name "Net-(U101-OUT)") (class "Default")
      (node (ref "L101") (pin "1") (pinfunction "1_1") (pintype "passive"))
      (node (ref "U101") (pin "2") (pinfunction "OUT_2") (pintype "power_in"))
      (node (ref "U111") (pin "1") (pinfunction "In_1") (pintype "passive"))
    )
    (net (code "51") (name "SIM_VDD") (class "Default")
      (node (ref "*1") (pin "6") (pinfunction "VCC_6") (pintype "passive"))
      (node (ref "C8") (pin "1") (pinfunction "1_1") (pintype "passive"))
      (node (ref "ESD1") (pin "4") (pinfunction "I5_4") (pintype "passive"))
      (node (ref "SIM1") (pin "30") (pinfunction "SIM_VDD_30") (pintype "output"))
    )
    (net (code "52") (name "SYS_5V") (class "Default")
      (node (ref "P1") (pin "7") (pinfunction "7_7") (pintype "passive"))
      (node (ref "P1") (pin "8") (pinfunction "8_8") (pintype "passive"))
      (node (ref "Q103") (pin "1") (pinfunction "D_1") (pintype "passive"))
      (node (ref "Q103") (pin "2") (pinfunction "D_2") (pintype "passive"))
      (node (ref "Q103") (pin "5") (pinfunction "D_5") (pintype "passive"))
      (node (ref "Q103") (pin "6") (pinfunction "D_6") (pintype "passive"))
    )
    (net (code "53") (name "VBAT") (class "Default")
      (node (ref "L102") (pin "2") (pinfunction "2_2") (pintype "passive"))
      (node (ref "P201") (pin "5") (pinfunction "VDD_5") (pintype "passive"))
      (node (ref "Q102") (pin "4") (pinfunction "S_4") (pintype "passive"))
      (node (ref "Q104") (pin "4") (pinfunction "S_4") (pintype "passive"))
      (node (ref "R101") (pin "2") (pinfunction "2_2") (pintype "passive"))
      (node (ref "R103") (pin "2") (pinfunction "2_2") (pintype "passive"))
      (node (ref "SIM1") (pin "55") (pinfunction "VBAT_55") (pintype "power_in"))
      (node (ref "SIM1") (pin "56") (pinfunction "VBAT_56") (pintype "power_in"))
      (node (ref "SIM1") (pin "57") (pinfunction "VBAT_57") (pintype "power_in"))
      (node (ref "U2") (pin "9") (pinfunction "VIN_9") (pintype "power_in"))
      (node (ref "U3") (pin "9") (pinfunction "VIN_9") (pintype "power_in"))
      (node (ref "U301") (pin "5") (pinfunction "VCC_5") (pintype "power_in"))
      (node (ref "VBAT1") (pin "1") (pintype "passive"))
    )
    (net (code "54") (name "VDD_3V3B") (class "Default")
      (node (ref "J1") (pin "1") (pinfunction "1_1") (pintype "passive"))
      (node (ref "J1") (pin "2") (pinfunction "2_2") (pintype "passive"))
      (node (ref "P1") (pin "3") (pinfunction "3_3") (pintype "passive"))
      (node (ref "P1") (pin "4") (pinfunction "4_4") (pintype "passive"))
    )
    (net (code "55") (name "VDD_5V") (class "Default")
      (node (ref "1") (pin "1") (pintype "passive"))
      (node (ref "P1") (pin "5") (pinfunction "5_5") (pintype "passive"))
      (node (ref "P1") (pin "6") (pinfunction "6_6") (pintype "passive"))
      (node (ref "Q201") (pin "4") (pinfunction "S_4") (pintype "passive"))
      (node (ref "R104") (pin "2") (pinfunction "2_2") (pintype "passive"))
    )
    (net (code "56") (name "unconnected-(*1-VPP-Pad2)") (class "Default")
      (node (ref "*1") (pin "2") (pinfunction "VPP_2") (pintype "passive"))
    )
    (net (code "57") (name "unconnected-(ESD1-I4-Pad3)") (class "Default")
      (node (ref "ESD1") (pin "3") (pinfunction "I4_3") (pintype "passive"))
    )
    (net (code "58") (name "unconnected-(J101-Pad1)") (class "Default")
      (node (ref "J101") (pin "1") (pinfunction "1_1") (pintype "passive"))
    )
    (net (code "59") (name "unconnected-(P1-Pad9)") (class "Default")
      (node (ref "P1") (pin "9") (pinfunction "9_9") (pintype "passive"))
    )
    (net (code "60") (name "unconnected-(P1-Pad10)") (class "Default")
      (node (ref "P1") (pin "10") (pinfunction "10_10") (pintype "passive"))
    )
    (net (code "61") (name "unconnected-(P1-Pad12)") (class "Default")
      (node (ref "P1") (pin "12") (pinfunction "12_12") (pintype "passive"))
    )
    (net (code "62") (name "unconnected-(P1-Pad14)") (class "Default")
      (node (ref "P1") (pin "14") (pinfunction "14_14") (pintype "passive"))
    )
    (net (code "63") (name "unconnected-(P1-Pad15)") (class "Default")
      (node (ref "P1") (pin "15") (pinfunction "15_15") (pintype "passive"))
    )
    (net (code "64") (name "unconnected-(P1-Pad16)") (class "Default")
      (node (ref "P1") (pin "16") (pinfunction "16_16") (pintype "passive"))
    )
    (net (code "65") (name "unconnected-(P1-Pad17)") (class "Default")
      (node (ref "P1") (pin "17") (pinfunction "17_17") (pintype "passive"))
    )
    (net (code "66") (name "unconnected-(P1-Pad18)") (class "Default")
      (node (ref "P1") (pin "18") (pinfunction "18_18") (pintype "passive"))
    )
    (net (code "67") (name "unconnected-(P1-Pad19)") (class "Default")
      (node (ref "P1") (pin "19") (pinfunction "19_19") (pintype "passive"))
    )
    (net (code "68") (name "unconnected-(P1-Pad20)") (class "Default")
      (node (ref "P1") (pin "20") (pinfunction "20_20") (pintype "passive"))
    )
    (net (code "69") (name "unconnected-(P1-Pad21)") (class "Default")
      (node (ref "P1") (pin "21") (pinfunction "21_21") (pintype "passive"))
    )
    (net (code "70") (name "unconnected-(P1-Pad22)") (class "Default")
      (node (ref "P1") (pin "22") (pinfunction "22_22") (pintype "passive"))
    )
    (net (code "71") (name "unconnected-(P1-Pad23)") (class "Default")
      (node (ref "P1") (pin "23") (pinfunction "23_23") (pintype "passive"))
    )
    (net (code "72") (name "unconnected-(P1-Pad24)") (class "Default")
      (node (ref "P1") (pin "24") (pinfunction "24_24") (pintype "passive"))
    )
    (net (code "73") (name "unconnected-(P1-Pad25)") (class "Default")
      (node (ref "P1") (pin "25") (pinfunction "25_25") (pintype "passive"))
    )
    (net (code "74") (name "unconnected-(P1-Pad26)") (class "Default")
      (node (ref "P1") (pin "26") (pinfunction "26_26") (pintype "passive"))
    )
    (net (code "75") (name "unconnected-(P1-Pad27)") (class "Default")
      (node (ref "P1") (pin "27") (pinfunction "27_27") (pintype "passive"))
    )
    (net (code "76") (name "unconnected-(P1-Pad28)") (class "Default")
      (node (ref "P1") (pin "28") (pinfunction "28_28") (pintype "passive"))
    )
    (net (code "77") (name "unconnected-(P1-Pad29)") (class "Default")
      (node (ref "P1") (pin "29") (pinfunction "29_29") (pintype "passive"))
    )
    (net (code "78") (name "unconnected-(P1-Pad30)") (class "Default")
      (node (ref "P1") (pin "30") (pinfunction "30_30") (pintype "passive"))
    )
    (net (code "79") (name "unconnected-(P1-Pad31)") (class "Default")
      (node (ref "P1") (pin "31") (pinfunction "31_31") (pintype "passive"))
    )
    (net (code "80") (name "unconnected-(P1-Pad32)") (class "Default")
      (node (ref "P1") (pin "32") (pinfunction "32_32") (pintype "passive"))
    )
    (net (code "81") (name "unconnected-(P1-Pad33)") (class "Default")
      (node (ref "P1") (pin "33") (pinfunction "33_33") (pintype "passive"))
    )
    (net (code "82") (name "unconnected-(P1-Pad35)") (class "Default")
      (node (ref "P1") (pin "35") (pinfunction "35_35") (pintype "passive"))
    )
    (net (code "83") (name "unconnected-(P1-Pad36)") (class "Default")
      (node (ref "P1") (pin "36") (pinfunction "36_36") (pintype "passive"))
    )
    (net (code "84") (name "unconnected-(P1-Pad37)") (class "Default")
      (node (ref "P1") (pin "37") (pinfunction "37_37") (pintype "passive"))
    )
    (net (code "85") (name "unconnected-(P1-Pad38)") (class "Default")
      (node (ref "P1") (pin "38") (pinfunction "38_38") (pintype "passive"))
    )
    (net (code "86") (name "unconnected-(P1-Pad39)") (class "Default")
      (node (ref "P1") (pin "39") (pinfunction "39_39") (pintype "passive"))
    )
    (net (code "87") (name "unconnected-(P1-Pad40)") (class "Default")
      (node (ref "P1") (pin "40") (pinfunction "40_40") (pintype "passive"))
    )
    (net (code "88") (name "unconnected-(P2-41-Pad1)") (class "Default")
      (node (ref "P2") (pin "1") (pinfunction "41_1") (pintype "passive"))
    )
    (net (code "89") (name "unconnected-(P2-42-Pad2)") (class "Default")
      (node (ref "P2") (pin "2") (pinfunction "42_2") (pintype "passive"))
    )
    (net (code "90") (name "unconnected-(P3-Pad3)") (class "Default")
      (node (ref "P3") (pin "3") (pinfunction "3_3") (pintype "passive"))
    )
    (net (code "91") (name "unconnected-(P3-Pad4)") (class "Default")
      (node (ref "P3") (pin "4") (pinfunction "4_4") (pintype "passive"))
    )
    (net (code "92") (name "unconnected-(P3-Pad5)") (class "Default")
      (node (ref "P3") (pin "5") (pinfunction "5_5") (pintype "passive"))
    )
    (net (code "93") (name "unconnected-(P3-Pad6)") (class "Default")
      (node (ref "P3") (pin "6") (pinfunction "6_6") (pintype "passive"))
    )
    (net (code "94") (name "unconnected-(P3-Pad7)") (class "Default")
      (node (ref "P3") (pin "7") (pinfunction "7_7") (pintype "passive"))
    )
    (net (code "95") (name "unconnected-(P3-Pad11)") (class "Default")
      (node (ref "P3") (pin "11") (pinfunction "11_11") (pintype "passive"))
    )
    (net (code "96") (name "unconnected-(P3-Pad13)") (class "Default")
      (node (ref "P3") (pin "13") (pinfunction "13_13") (pintype "passive"))
    )
    (net (code "97") (name "unconnected-(P3-Pad14)") (class "Default")
      (node (ref "P3") (pin "14") (pinfunction "14_14") (pintype "passive"))
    )
    (net (code "98") (name "unconnected-(P3-Pad15)") (class "Default")
      (node (ref "P3") (pin "15") (pinfunction "15_15") (pintype "passive"))
    )
    (net (code "99") (name "unconnected-(P3-Pad16)") (class "Default")
      (node (ref "P3") (pin "16") (pinfunction "16_16") (pintype "passive"))
    )
    (net (code "100") (name "unconnected-(P3-Pad17)") (class "Default")
      (node (ref "P3") (pin "17") (pinfunction "17_17") (pintype "passive"))
    )
    (net (code "101") (name "unconnected-(P3-Pad18)") (class "Default")
      (node (ref "P3") (pin "18") (pinfunction "18_18") (pintype "passive"))
    )
    (net (code "102") (name "unconnected-(P3-Pad19)") (class "Default")
      (node (ref "P3") (pin "19") (pinfunction "19_19") (pintype "passive"))
    )
    (net (code "103") (name "unconnected-(P3-Pad20)") (class "Default")
      (node (ref "P3") (pin "20") (pinfunction "20_20") (pintype "passive"))
    )
    (net (code "104") (name "unconnected-(P3-Pad21)") (class "Default")
      (node (ref "P3") (pin "21") (pinfunction "21_21") (pintype "passive"))
    )
    (net (code "105") (name "unconnected-(P3-Pad22)") (class "Default")
      (node (ref "P3") (pin "22") (pinfunction "22_22") (pintype "passive"))
    )
    (net (code "106") (name "unconnected-(P3-Pad23)") (class "Default")
      (node (ref "P3") (pin "23") (pinfunction "23_23") (pintype "passive"))
    )
    (net (code "107") (name "unconnected-(P3-Pad24)") (class "Default")
      (node (ref "P3") (pin "24") (pinfunction "24_24") (pintype "passive"))
    )
    (net (code "108") (name "unconnected-(P3-Pad25)") (class "Default")
      (node (ref "P3") (pin "25") (pinfunction "25_25") (pintype "passive"))
    )
    (net (code "109") (name "unconnected-(P3-Pad26)") (class "Default")
      (node (ref "P3") (pin "26") (pinfunction "26_26") (pintype "passive"))
    )
    (net (code "110") (name "unconnected-(P3-Pad27)") (class "Default")
      (node (ref "P3") (pin "27") (pinfunction "27_27") (pintype "passive"))
    )
    (net (code "111") (name "unconnected-(P3-Pad28)") (class "Default")
      (node (ref "P3") (pin "28") (pinfunction "28_28") (pintype "passive"))
    )
    (net (code "112") (name "unconnected-(P3-Pad29)") (class "Default")
      (node (ref "P3") (pin "29") (pinfunction "29_29") (pintype "passive"))
    )
    (net (code "113") (name "unconnected-(P3-Pad30)") (class "Default")
      (node (ref "P3") (pin "30") (pinfunction "30_30") (pintype "passive"))
    )
    (net (code "114") (name "unconnected-(P3-Pad31)") (class "Default")
      (node (ref "P3") (pin "31") (pinfunction "31_31") (pintype "passive"))
    )
    (net (code "115") (name "unconnected-(P3-Pad32)") (class "Default")
      (node (ref "P3") (pin "32") (pinfunction "32_32") (pintype "passive"))
    )
    (net (code "116") (name "unconnected-(P3-Pad33)") (class "Default")
      (node (ref "P3") (pin "33") (pinfunction "33_33") (pintype "passive"))
    )
    (net (code "117") (name "unconnected-(P3-Pad34)") (class "Default")
      (node (ref "P3") (pin "34") (pinfunction "34_34") (pintype "passive"))
    )
    (net (code "118") (name "unconnected-(P3-Pad35)") (class "Default")
      (node (ref "P3") (pin "35") (pinfunction "35_35") (pintype "passive"))
    )
    (net (code "119") (name "unconnected-(P3-Pad36)") (class "Default")
      (node (ref "P3") (pin "36") (pinfunction "36_36") (pintype "passive"))
    )
    (net (code "120") (name "unconnected-(P3-Pad37)") (class "Default")
      (node (ref "P3") (pin "37") (pinfunction "37_37") (pintype "passive"))
    )
    (net (code "121") (name "unconnected-(P3-Pad38)") (class "Default")
      (node (ref "P3") (pin "38") (pinfunction "38_38") (pintype "passive"))
    )
    (net (code "122") (name "unconnected-(P3-Pad39)") (class "Default")
      (node (ref "P3") (pin "39") (pinfunction "39_39") (pintype "passive"))
    )
    (net (code "123") (name "unconnected-(P3-Pad40)") (class "Default")
      (node (ref "P3") (pin "40") (pinfunction "40_40") (pintype "passive"))
    )
    (net (code "124") (name "unconnected-(P4-41-Pad1)") (class "Default")
      (node (ref "P4") (pin "1") (pinfunction "41_1") (pintype "passive"))
    )
    (net (code "125") (name "unconnected-(P4-42-Pad2)") (class "Default")
      (node (ref "P4") (pin "2") (pinfunction "42_2") (pintype "passive"))
    )
    (net (code "126") (name "unconnected-(P4-43-Pad3)") (class "Default")
      (node (ref "P4") (pin "3") (pinfunction "43_3") (pintype "passive"))
    )
    (net (code "127") (name "unconnected-(P4-44-Pad4)") (class "Default")
      (node (ref "P4") (pin "4") (pinfunction "44_4") (pintype "passive"))
    )
    (net (code "128") (name "unconnected-(P4-45-Pad5)") (class "Default")
      (node (ref "P4") (pin "5") (pinfunction "45_5") (pintype "passive"))
    )
    (net (code "129") (name "unconnected-(P4-46-Pad6)") (class "Default")
      (node (ref "P4") (pin "6") (pinfunction "46_6") (pintype "passive"))
    )
    (net (code "130") (name "unconnected-(P201-INB--Pad4)") (class "Default")
      (node (ref "P201") (pin "4") (pinfunction "INB-_4") (pintype "passive"))
    )
    (net (code "131") (name "unconnected-(P201-OUTB-Pad6)") (class "Default")
      (node (ref "P201") (pin "6") (pinfunction "OUTB_6") (pintype "passive"))
    )
    (net (code "132") (name "unconnected-(SIM1-ADC-Pad25)") (class "Default")
      (node (ref "SIM1") (pin "25") (pinfunction "ADC_25") (pintype "passive"))
    )
    (net (code "133") (name "unconnected-(SIM1-CTS-Pad7)") (class "Default")
      (node (ref "SIM1") (pin "7") (pinfunction "CTS_7") (pintype "passive"))
    )
    (net (code "134") (name "unconnected-(SIM1-DCD-Pad5)") (class "Default")
      (node (ref "SIM1") (pin "5") (pinfunction "DCD_5") (pintype "passive"))
    )
    (net (code "135") (name "unconnected-(SIM1-DISP_CLK-Pad11)") (class "Default")
      (node (ref "SIM1") (pin "11") (pinfunction "DISP_CLK_11") (pintype "passive"))
    )
    (net (code "136") (name "unconnected-(SIM1-DISP_CS-Pad14)") (class "Default")
      (node (ref "SIM1") (pin "14") (pinfunction "DISP_CS_14") (pintype "passive"))
    )
    (net (code "137") (name "unconnected-(SIM1-DISP_DATA-Pad12)") (class "Default")
      (node (ref "SIM1") (pin "12") (pinfunction "DISP_DATA_12") (pintype "passive"))
    )
    (net (code "138") (name "unconnected-(SIM1-DISP_D{slash}C-Pad13)") (class "Default")
      (node (ref "SIM1") (pin "13") (pinfunction "DISP_D/C_13") (pintype "passive"))
    )
    (net (code "139") (name "unconnected-(SIM1-DSR-Pad6)") (class "Default")
      (node (ref "SIM1") (pin "6") (pinfunction "DSR_6") (pintype "passive"))
    )
    (net (code "140") (name "unconnected-(SIM1-DTR-Pad3)") (class "Default")
      (node (ref "SIM1") (pin "3") (pinfunction "DTR_3") (pintype "passive"))
    )
    (net (code "141") (name "unconnected-(SIM1-GPIO1-Pad40)") (class "Default")
      (node (ref "SIM1") (pin "40") (pinfunction "GPIO1_40") (pintype "bidirectional"))
    )
    (net (code "142") (name "unconnected-(SIM1-GPIO2-Pad41)") (class "Default")
      (node (ref "SIM1") (pin "41") (pinfunction "GPIO2_41") (pintype "bidirectional"))
    )
    (net (code "143") (name "unconnected-(SIM1-GPIO3-Pad42)") (class "Default")
      (node (ref "SIM1") (pin "42") (pinfunction "GPIO3_42") (pintype "bidirectional"))
    )
    (net (code "144") (name "unconnected-(SIM1-GPIO4-Pad43)") (class "Default")
      (node (ref "SIM1") (pin "43") (pinfunction "GPIO4_43") (pintype "bidirectional"))
    )
    (net (code "145") (name "unconnected-(SIM1-GPIO5-Pad44)") (class "Default")
      (node (ref "SIM1") (pin "44") (pinfunction "GPIO5_44") (pintype "bidirectional"))
    )
    (net (code "146") (name "unconnected-(SIM1-GPIO6-Pad47)") (class "Default")
      (node (ref "SIM1") (pin "47") (pinfunction "GPIO6_47") (pintype "bidirectional"))
    )
    (net (code "147") (name "unconnected-(SIM1-GPIO7-Pad48)") (class "Default")
      (node (ref "SIM1") (pin "48") (pinfunction "GPIO7_48") (pintype "bidirectional"))
    )
    (net (code "148") (name "unconnected-(SIM1-GPIO8-Pad49)") (class "Default")
      (node (ref "SIM1") (pin "49") (pinfunction "GPIO8_49") (pintype "bidirectional"))
    )
    (net (code "149") (name "unconnected-(SIM1-GPIO9-Pad50)") (class "Default")
      (node (ref "SIM1") (pin "50") (pinfunction "GPIO9_50") (pintype "bidirectional"))
    )
    (net (code "150") (name "unconnected-(SIM1-GPIO10-Pad51)") (class "Default")
      (node (ref "SIM1") (pin "51") (pinfunction "GPIO10_51") (pintype "bidirectional"))
    )
    (net (code "151") (name "unconnected-(SIM1-GPIO11-Pad67)") (class "Default")
      (node (ref "SIM1") (pin "67") (pinfunction "GPIO11_67") (pintype "bidirectional"))
    )
    (net (code "152") (name "unconnected-(SIM1-GPIO12-Pad68)") (class "Default")
      (node (ref "SIM1") (pin "68") (pinfunction "GPIO12_68") (pintype "bidirectional"))
    )
    (net (code "153") (name "unconnected-(SIM1-LINEIN_L-Pad24)") (class "Default")
      (node (ref "SIM1") (pin "24") (pinfunction "LINEIN_L_24") (pintype "passive"))
    )
    (net (code "154") (name "unconnected-(SIM1-LINEIN_R-Pad23)") (class "Default")
      (node (ref "SIM1") (pin "23") (pinfunction "LINEIN_R_23") (pintype "passive"))
    )
    (net (code "155") (name "unconnected-(SIM1-NRESET-Pad16)") (class "Default")
      (node (ref "SIM1") (pin "16") (pinfunction "NRESET_16") (pintype "input"))
    )
    (net (code "156") (name "unconnected-(SIM1-PWM1-Pad35)") (class "Default")
      (node (ref "SIM1") (pin "35") (pinfunction "PWM1_35") (pintype "output"))
    )
    (net (code "157") (name "unconnected-(SIM1-PWM2-Pad36)") (class "Default")
      (node (ref "SIM1") (pin "36") (pinfunction "PWM2_36") (pintype "output"))
    )
    (net (code "158") (name "unconnected-(SIM1-PWRKEY_out-Pad2)") (class "Default")
      (node (ref "SIM1") (pin "2") (pinfunction "PWRKEY_out_2") (pintype "output"))
    )
    (net (code "159") (name "unconnected-(SIM1-RI-Pad4)") (class "Default")
      (node (ref "SIM1") (pin "4") (pinfunction "RI_4") (pintype "passive"))
    )
    (net (code "160") (name "unconnected-(SIM1-RTS-Pad8)") (class "Default")
      (node (ref "SIM1") (pin "8") (pinfunction "RTS_8") (pintype "passive"))
    )
    (net (code "161") (name "unconnected-(SIM1-RXD-Pad10)") (class "Default")
      (node (ref "SIM1") (pin "10") (pinfunction "RXD_10") (pintype "input"))
    )
    (net (code "162") (name "unconnected-(SIM1-SCL-Pad38)") (class "Default")
      (node (ref "SIM1") (pin "38") (pinfunction "SCL_38") (pintype "output"))
    )
    (net (code "163") (name "unconnected-(SIM1-SDA-Pad37)") (class "Default")
      (node (ref "SIM1") (pin "37") (pinfunction "SDA_37") (pintype "bidirectional"))
    )
    (net (code "164") (name "unconnected-(SIM1-SIM_PRS-Pad34)") (class "Default")
      (node (ref "SIM1") (pin "34") (pinfunction "SIM_PRS_34") (pintype "passive"))
    )
    (net (code "165") (name "unconnected-(SIM1-STATUS-Pad66)") (class "Default")
      (node (ref "SIM1") (pin "66") (pinfunction "STATUS_66") (pintype "output"))
    )
    (net (code "166") (name "unconnected-(SIM1-TXD-Pad9)") (class "Default")
      (node (ref "SIM1") (pin "9") (pinfunction "TXD_9") (pintype "output"))
    )
    (net (code "167") (name "unconnected-(SIM1-VDD_EXT_2V8-Pad15)") (class "Default")
      (node (ref "SIM1") (pin "15") (pinfunction "VDD_EXT_2V8_15") (pintype "output"))
    )
    (net (code "168") (name "unconnected-(SIM1-VRTC-Pad26)") (class "Default")
      (node (ref "SIM1") (pin "26") (pinfunction "VRTC_26") (pintype "passive"))
    )
    (net (code "169") (name "unconnected-(U2-ISET-Pad10)") (class "Default")
      (node (ref "U2") (pin "10") (pinfunction "ISET_10") (pintype "input"))
    )
    (net (code "170") (name "unconnected-(U2-NC-Pad6)") (class "Default")
      (node (ref "U2") (pin "6") (pinfunction "NC_6") (pintype "passive"))
    )
    (net (code "171") (name "unconnected-(U3-ISET-Pad10)") (class "Default")
      (node (ref "U3") (pin "10") (pinfunction "ISET_10") (pintype "input"))
    )
    (net (code "172") (name "unconnected-(U3-NC-Pad6)") (class "Default")
      (node (ref "U3") (pin "6") (pinfunction "NC_6") (pintype "passive"))
    )
    (net (code "173") (name "unconnected-(U101-TAB-Pad6)") (class "Default")
      (node (ref "U101") (pin "6") (pinfunction "TAB_6") (pintype "power_in"))
    )
    (net (code "174") (name "unconnected-(U101-~{ON}{slash}OFF-Pad5)") (class "Default")
      (node (ref "U101") (pin "5") (pinfunction "~{ON}/OFF_5") (pintype "input"))
    )
    (net (code "175") (name "unconnected-(U301-NC-Pad1)") (class "Default")
      (node (ref "U301") (pin "1") (pinfunction "NC_1") (pintype "passive"))
    )
  )
)
